# yacc2buss.net
KiCad netlist of a schematic drawn in EAGLE
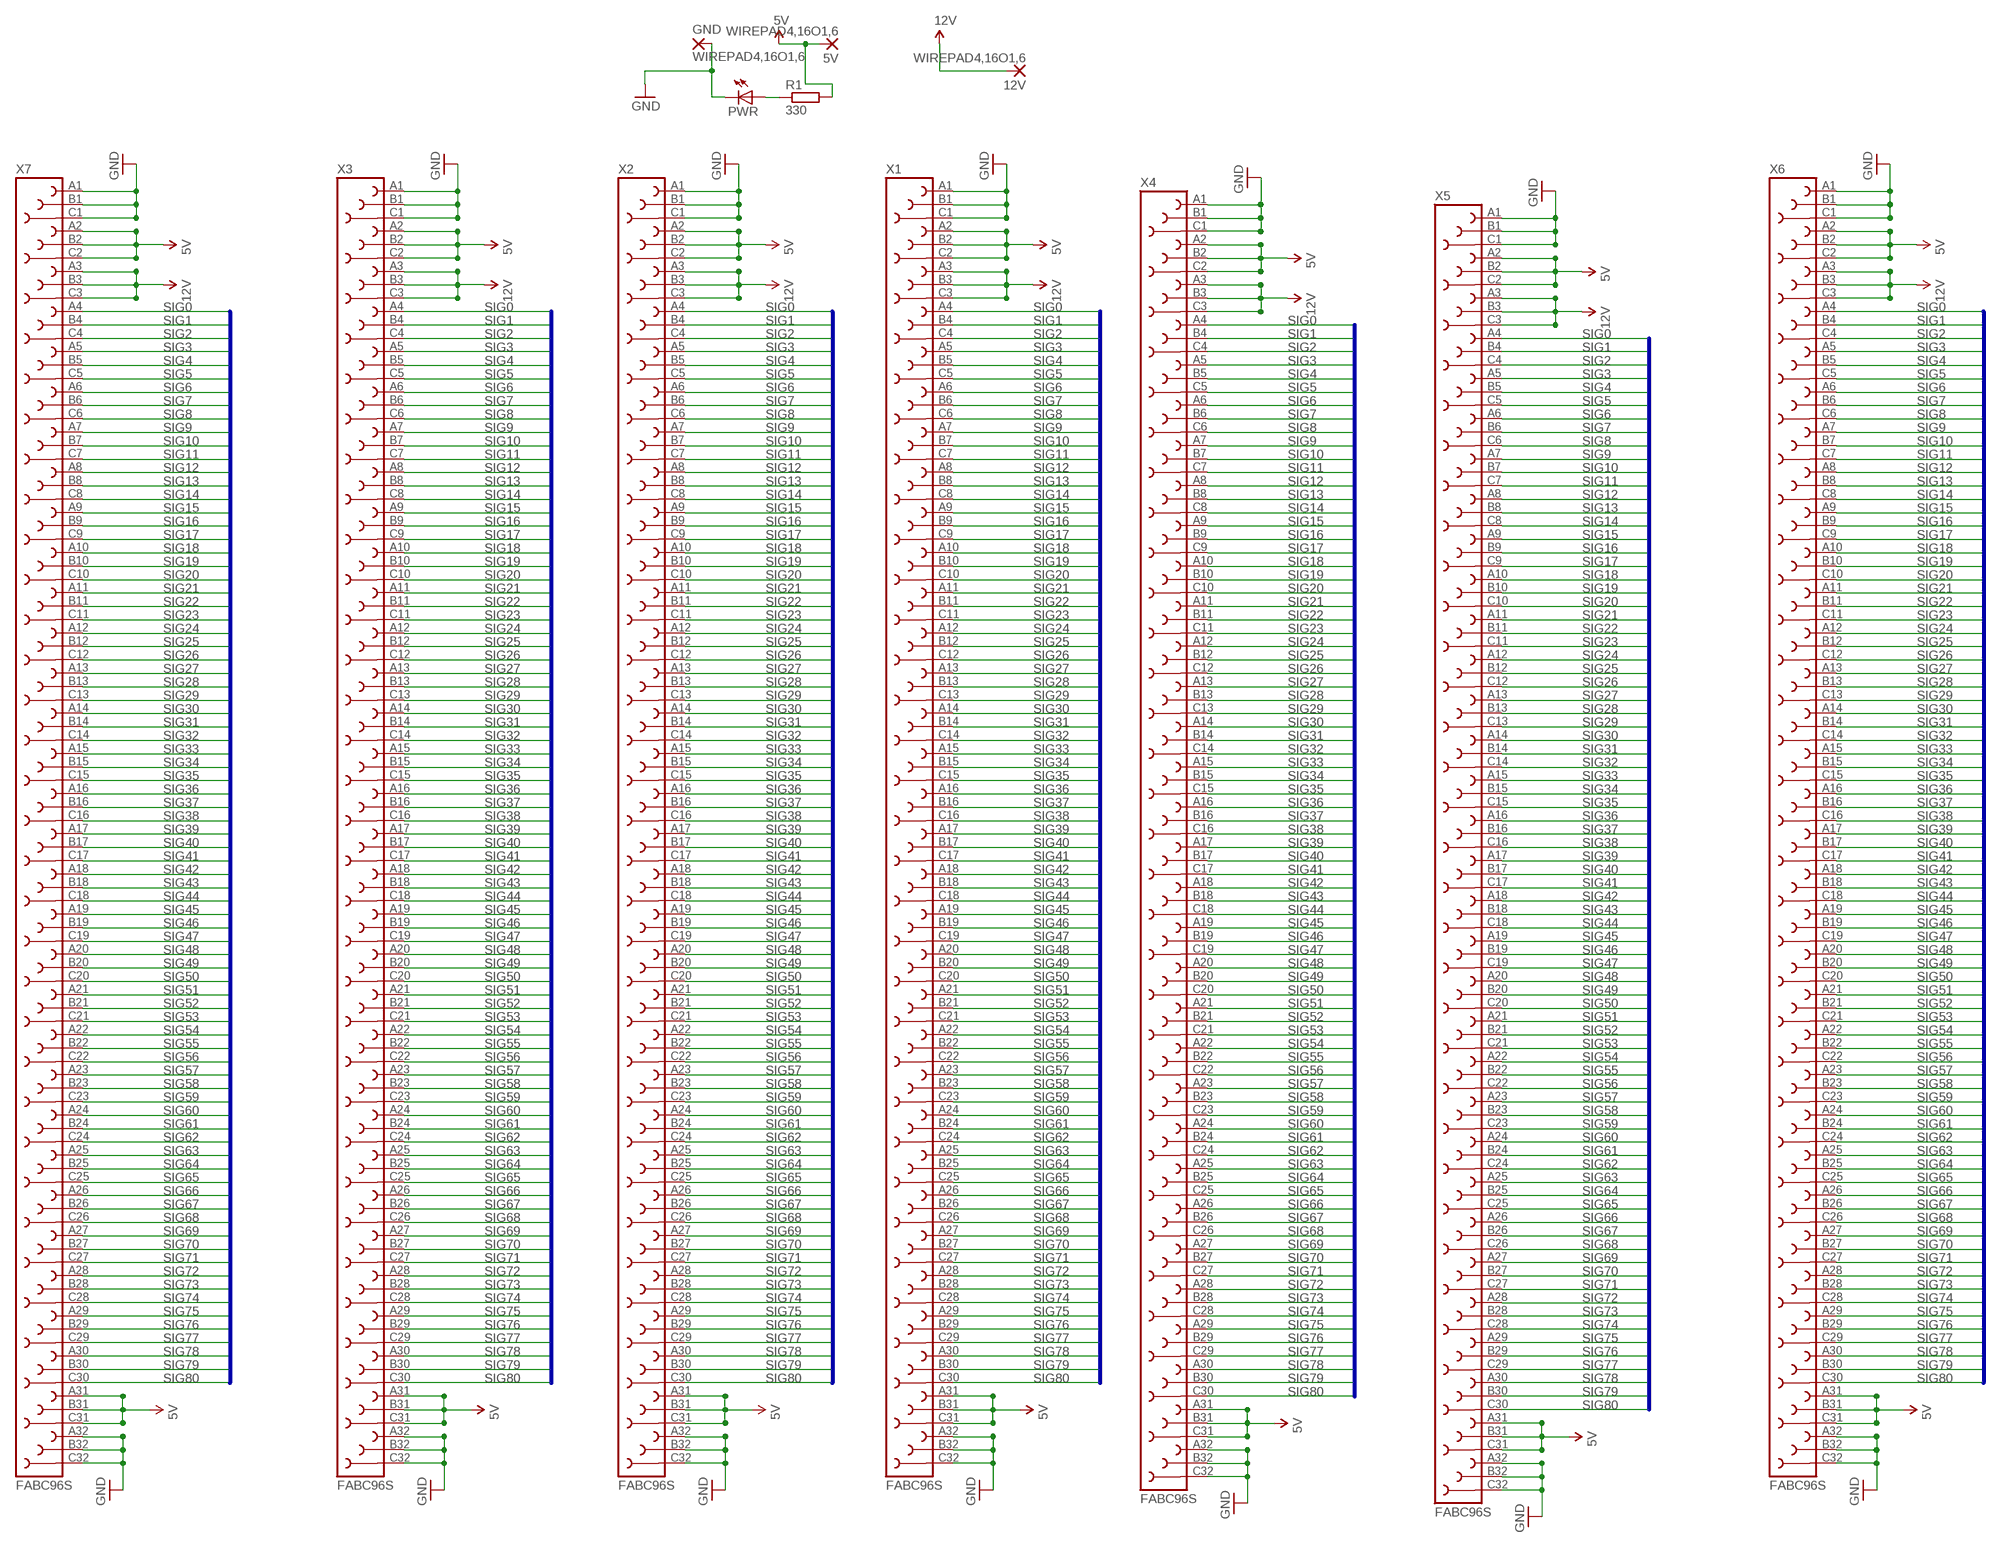
[diagram p0: schematic, sheet 1]

(export (version "E")
  (design (tool "Eeschema 10.0.6"))
  (components
    (comp (ref "5V")
      (value "WIREPAD4,16O1,6")
      (footprint "eagle-import:4,16O1,6")
      (libsource (lib "eagle-import") (part "WIREPAD4,16O1,6"))
    )
    (comp (ref "12V")
      (value "WIREPAD4,16O1,6")
      (footprint "eagle-import:4,16O1,6")
      (libsource (lib "eagle-import") (part "WIREPAD4,16O1,6"))
    )
    (comp (ref "GND")
      (value "WIREPAD4,16O1,6")
      (footprint "eagle-import:4,16O1,6")
      (libsource (lib "eagle-import") (part "WIREPAD4,16O1,6"))
    )
    (comp (ref "PWR")
      (value "LED5MM")
      (footprint "eagle-import:LED5MM")
      (libsource (lib "eagle-import") (part "LED5MM"))
    )
    (comp (ref "R1")
      (value "330")
      (footprint "eagle-import:0207_10")
      (libsource (lib "eagle-import") (part "R0207/10"))
    )
    (comp (ref "X1")
      (value "FABC96S")
      (footprint "eagle-import:FABC96S")
      (libsource (lib "eagle-import") (part "FABC96S"))
    )
    (comp (ref "X2")
      (value "FABC96S")
      (footprint "eagle-import:FABC96S")
      (libsource (lib "eagle-import") (part "FABC96S"))
    )
    (comp (ref "X3")
      (value "FABC96S")
      (footprint "eagle-import:FABC96S")
      (libsource (lib "eagle-import") (part "FABC96S"))
    )
    (comp (ref "X4")
      (value "FABC96S")
      (footprint "eagle-import:FABC96S")
      (libsource (lib "eagle-import") (part "FABC96S"))
    )
    (comp (ref "X5")
      (value "FABC96S")
      (footprint "eagle-import:FABC96S")
      (libsource (lib "eagle-import") (part "FABC96S"))
    )
    (comp (ref "X6")
      (value "FABC96S")
      (footprint "eagle-import:FABC96S")
      (libsource (lib "eagle-import") (part "FABC96S"))
    )
    (comp (ref "X7")
      (value "FABC96S")
      (footprint "eagle-import:FABC96S")
      (libsource (lib "eagle-import") (part "FABC96S"))
    )
  )
  (nets
    (net (code "1") (name "/SIG0") (class "Default")
      (node (ref "X1") (pin "A4") (pinfunction "A4_A4") (pintype "passive"))
      (node (ref "X2") (pin "A4") (pinfunction "A4_A4") (pintype "passive"))
      (node (ref "X3") (pin "A4") (pinfunction "A4_A4") (pintype "passive"))
      (node (ref "X4") (pin "A4") (pinfunction "A4_A4") (pintype "passive"))
      (node (ref "X5") (pin "A4") (pinfunction "A4_A4") (pintype "passive"))
      (node (ref "X6") (pin "A4") (pinfunction "A4_A4") (pintype "passive"))
      (node (ref "X7") (pin "A4") (pinfunction "A4_A4") (pintype "passive"))
    )
    (net (code "2") (name "/SIG1") (class "Default")
      (node (ref "X1") (pin "B4") (pinfunction "B4_B4") (pintype "passive"))
      (node (ref "X2") (pin "B4") (pinfunction "B4_B4") (pintype "passive"))
      (node (ref "X3") (pin "B4") (pinfunction "B4_B4") (pintype "passive"))
      (node (ref "X4") (pin "B4") (pinfunction "B4_B4") (pintype "passive"))
      (node (ref "X5") (pin "B4") (pinfunction "B4_B4") (pintype "passive"))
      (node (ref "X6") (pin "B4") (pinfunction "B4_B4") (pintype "passive"))
      (node (ref "X7") (pin "B4") (pinfunction "B4_B4") (pintype "passive"))
    )
    (net (code "3") (name "/SIG2") (class "Default")
      (node (ref "X1") (pin "C4") (pinfunction "C4_C4") (pintype "passive"))
      (node (ref "X2") (pin "C4") (pinfunction "C4_C4") (pintype "passive"))
      (node (ref "X3") (pin "C4") (pinfunction "C4_C4") (pintype "passive"))
      (node (ref "X4") (pin "C4") (pinfunction "C4_C4") (pintype "passive"))
      (node (ref "X5") (pin "C4") (pinfunction "C4_C4") (pintype "passive"))
      (node (ref "X6") (pin "C4") (pinfunction "C4_C4") (pintype "passive"))
      (node (ref "X7") (pin "C4") (pinfunction "C4_C4") (pintype "passive"))
    )
    (net (code "4") (name "/SIG3") (class "Default")
      (node (ref "X1") (pin "A5") (pinfunction "A5_A5") (pintype "passive"))
      (node (ref "X2") (pin "A5") (pinfunction "A5_A5") (pintype "passive"))
      (node (ref "X3") (pin "A5") (pinfunction "A5_A5") (pintype "passive"))
      (node (ref "X4") (pin "A5") (pinfunction "A5_A5") (pintype "passive"))
      (node (ref "X5") (pin "A5") (pinfunction "A5_A5") (pintype "passive"))
      (node (ref "X6") (pin "A5") (pinfunction "A5_A5") (pintype "passive"))
      (node (ref "X7") (pin "A5") (pinfunction "A5_A5") (pintype "passive"))
    )
    (net (code "5") (name "/SIG4") (class "Default")
      (node (ref "X1") (pin "B5") (pinfunction "B5_B5") (pintype "passive"))
      (node (ref "X2") (pin "B5") (pinfunction "B5_B5") (pintype "passive"))
      (node (ref "X3") (pin "B5") (pinfunction "B5_B5") (pintype "passive"))
      (node (ref "X4") (pin "B5") (pinfunction "B5_B5") (pintype "passive"))
      (node (ref "X5") (pin "B5") (pinfunction "B5_B5") (pintype "passive"))
      (node (ref "X6") (pin "B5") (pinfunction "B5_B5") (pintype "passive"))
      (node (ref "X7") (pin "B5") (pinfunction "B5_B5") (pintype "passive"))
    )
    (net (code "6") (name "/SIG5") (class "Default")
      (node (ref "X1") (pin "C5") (pinfunction "C5_C5") (pintype "passive"))
      (node (ref "X2") (pin "C5") (pinfunction "C5_C5") (pintype "passive"))
      (node (ref "X3") (pin "C5") (pinfunction "C5_C5") (pintype "passive"))
      (node (ref "X4") (pin "C5") (pinfunction "C5_C5") (pintype "passive"))
      (node (ref "X5") (pin "C5") (pinfunction "C5_C5") (pintype "passive"))
      (node (ref "X6") (pin "C5") (pinfunction "C5_C5") (pintype "passive"))
      (node (ref "X7") (pin "C5") (pinfunction "C5_C5") (pintype "passive"))
    )
    (net (code "7") (name "/SIG6") (class "Default")
      (node (ref "X1") (pin "A6") (pinfunction "A6_A6") (pintype "passive"))
      (node (ref "X2") (pin "A6") (pinfunction "A6_A6") (pintype "passive"))
      (node (ref "X3") (pin "A6") (pinfunction "A6_A6") (pintype "passive"))
      (node (ref "X4") (pin "A6") (pinfunction "A6_A6") (pintype "passive"))
      (node (ref "X5") (pin "A6") (pinfunction "A6_A6") (pintype "passive"))
      (node (ref "X6") (pin "A6") (pinfunction "A6_A6") (pintype "passive"))
      (node (ref "X7") (pin "A6") (pinfunction "A6_A6") (pintype "passive"))
    )
    (net (code "8") (name "/SIG7") (class "Default")
      (node (ref "X1") (pin "B6") (pinfunction "B6_B6") (pintype "passive"))
      (node (ref "X2") (pin "B6") (pinfunction "B6_B6") (pintype "passive"))
      (node (ref "X3") (pin "B6") (pinfunction "B6_B6") (pintype "passive"))
      (node (ref "X4") (pin "B6") (pinfunction "B6_B6") (pintype "passive"))
      (node (ref "X5") (pin "B6") (pinfunction "B6_B6") (pintype "passive"))
      (node (ref "X6") (pin "B6") (pinfunction "B6_B6") (pintype "passive"))
      (node (ref "X7") (pin "B6") (pinfunction "B6_B6") (pintype "passive"))
    )
    (net (code "9") (name "/SIG8") (class "Default")
      (node (ref "X1") (pin "C6") (pinfunction "C6_C6") (pintype "passive"))
      (node (ref "X2") (pin "C6") (pinfunction "C6_C6") (pintype "passive"))
      (node (ref "X3") (pin "C6") (pinfunction "C6_C6") (pintype "passive"))
      (node (ref "X4") (pin "C6") (pinfunction "C6_C6") (pintype "passive"))
      (node (ref "X5") (pin "C6") (pinfunction "C6_C6") (pintype "passive"))
      (node (ref "X6") (pin "C6") (pinfunction "C6_C6") (pintype "passive"))
      (node (ref "X7") (pin "C6") (pinfunction "C6_C6") (pintype "passive"))
    )
    (net (code "10") (name "/SIG9") (class "Default")
      (node (ref "X1") (pin "A7") (pinfunction "A7_A7") (pintype "passive"))
      (node (ref "X2") (pin "A7") (pinfunction "A7_A7") (pintype "passive"))
      (node (ref "X3") (pin "A7") (pinfunction "A7_A7") (pintype "passive"))
      (node (ref "X4") (pin "A7") (pinfunction "A7_A7") (pintype "passive"))
      (node (ref "X5") (pin "A7") (pinfunction "A7_A7") (pintype "passive"))
      (node (ref "X6") (pin "A7") (pinfunction "A7_A7") (pintype "passive"))
      (node (ref "X7") (pin "A7") (pinfunction "A7_A7") (pintype "passive"))
    )
    (net (code "11") (name "/SIG10") (class "Default")
      (node (ref "X1") (pin "B7") (pinfunction "B7_B7") (pintype "passive"))
      (node (ref "X2") (pin "B7") (pinfunction "B7_B7") (pintype "passive"))
      (node (ref "X3") (pin "B7") (pinfunction "B7_B7") (pintype "passive"))
      (node (ref "X4") (pin "B7") (pinfunction "B7_B7") (pintype "passive"))
      (node (ref "X5") (pin "B7") (pinfunction "B7_B7") (pintype "passive"))
      (node (ref "X6") (pin "B7") (pinfunction "B7_B7") (pintype "passive"))
      (node (ref "X7") (pin "B7") (pinfunction "B7_B7") (pintype "passive"))
    )
    (net (code "12") (name "/SIG11") (class "Default")
      (node (ref "X1") (pin "C7") (pinfunction "C7_C7") (pintype "passive"))
      (node (ref "X2") (pin "C7") (pinfunction "C7_C7") (pintype "passive"))
      (node (ref "X3") (pin "C7") (pinfunction "C7_C7") (pintype "passive"))
      (node (ref "X4") (pin "C7") (pinfunction "C7_C7") (pintype "passive"))
      (node (ref "X5") (pin "C7") (pinfunction "C7_C7") (pintype "passive"))
      (node (ref "X6") (pin "C7") (pinfunction "C7_C7") (pintype "passive"))
      (node (ref "X7") (pin "C7") (pinfunction "C7_C7") (pintype "passive"))
    )
    (net (code "13") (name "/SIG12") (class "Default")
      (node (ref "X1") (pin "A8") (pinfunction "A8_A8") (pintype "passive"))
      (node (ref "X2") (pin "A8") (pinfunction "A8_A8") (pintype "passive"))
      (node (ref "X3") (pin "A8") (pinfunction "A8_A8") (pintype "passive"))
      (node (ref "X4") (pin "A8") (pinfunction "A8_A8") (pintype "passive"))
      (node (ref "X5") (pin "A8") (pinfunction "A8_A8") (pintype "passive"))
      (node (ref "X6") (pin "A8") (pinfunction "A8_A8") (pintype "passive"))
      (node (ref "X7") (pin "A8") (pinfunction "A8_A8") (pintype "passive"))
    )
    (net (code "14") (name "/SIG13") (class "Default")
      (node (ref "X1") (pin "B8") (pinfunction "B8_B8") (pintype "passive"))
      (node (ref "X2") (pin "B8") (pinfunction "B8_B8") (pintype "passive"))
      (node (ref "X3") (pin "B8") (pinfunction "B8_B8") (pintype "passive"))
      (node (ref "X4") (pin "B8") (pinfunction "B8_B8") (pintype "passive"))
      (node (ref "X5") (pin "B8") (pinfunction "B8_B8") (pintype "passive"))
      (node (ref "X6") (pin "B8") (pinfunction "B8_B8") (pintype "passive"))
      (node (ref "X7") (pin "B8") (pinfunction "B8_B8") (pintype "passive"))
    )
    (net (code "15") (name "/SIG14") (class "Default")
      (node (ref "X1") (pin "C8") (pinfunction "C8_C8") (pintype "passive"))
      (node (ref "X2") (pin "C8") (pinfunction "C8_C8") (pintype "passive"))
      (node (ref "X3") (pin "C8") (pinfunction "C8_C8") (pintype "passive"))
      (node (ref "X4") (pin "C8") (pinfunction "C8_C8") (pintype "passive"))
      (node (ref "X5") (pin "C8") (pinfunction "C8_C8") (pintype "passive"))
      (node (ref "X6") (pin "C8") (pinfunction "C8_C8") (pintype "passive"))
      (node (ref "X7") (pin "C8") (pinfunction "C8_C8") (pintype "passive"))
    )
    (net (code "16") (name "/SIG15") (class "Default")
      (node (ref "X1") (pin "A9") (pinfunction "A9_A9") (pintype "passive"))
      (node (ref "X2") (pin "A9") (pinfunction "A9_A9") (pintype "passive"))
      (node (ref "X3") (pin "A9") (pinfunction "A9_A9") (pintype "passive"))
      (node (ref "X4") (pin "A9") (pinfunction "A9_A9") (pintype "passive"))
      (node (ref "X5") (pin "A9") (pinfunction "A9_A9") (pintype "passive"))
      (node (ref "X6") (pin "A9") (pinfunction "A9_A9") (pintype "passive"))
      (node (ref "X7") (pin "A9") (pinfunction "A9_A9") (pintype "passive"))
    )
    (net (code "17") (name "/SIG16") (class "Default")
      (node (ref "X1") (pin "B9") (pinfunction "B9_B9") (pintype "passive"))
      (node (ref "X2") (pin "B9") (pinfunction "B9_B9") (pintype "passive"))
      (node (ref "X3") (pin "B9") (pinfunction "B9_B9") (pintype "passive"))
      (node (ref "X4") (pin "B9") (pinfunction "B9_B9") (pintype "passive"))
      (node (ref "X5") (pin "B9") (pinfunction "B9_B9") (pintype "passive"))
      (node (ref "X6") (pin "B9") (pinfunction "B9_B9") (pintype "passive"))
      (node (ref "X7") (pin "B9") (pinfunction "B9_B9") (pintype "passive"))
    )
    (net (code "18") (name "/SIG17") (class "Default")
      (node (ref "X1") (pin "C9") (pinfunction "C9_C9") (pintype "passive"))
      (node (ref "X2") (pin "C9") (pinfunction "C9_C9") (pintype "passive"))
      (node (ref "X3") (pin "C9") (pinfunction "C9_C9") (pintype "passive"))
      (node (ref "X4") (pin "C9") (pinfunction "C9_C9") (pintype "passive"))
      (node (ref "X5") (pin "C9") (pinfunction "C9_C9") (pintype "passive"))
      (node (ref "X6") (pin "C9") (pinfunction "C9_C9") (pintype "passive"))
      (node (ref "X7") (pin "C9") (pinfunction "C9_C9") (pintype "passive"))
    )
    (net (code "19") (name "/SIG18") (class "Default")
      (node (ref "X1") (pin "A10") (pinfunction "A10_A10") (pintype "passive"))
      (node (ref "X2") (pin "A10") (pinfunction "A10_A10") (pintype "passive"))
      (node (ref "X3") (pin "A10") (pinfunction "A10_A10") (pintype "passive"))
      (node (ref "X4") (pin "A10") (pinfunction "A10_A10") (pintype "passive"))
      (node (ref "X5") (pin "A10") (pinfunction "A10_A10") (pintype "passive"))
      (node (ref "X6") (pin "A10") (pinfunction "A10_A10") (pintype "passive"))
      (node (ref "X7") (pin "A10") (pinfunction "A10_A10") (pintype "passive"))
    )
    (net (code "20") (name "/SIG19") (class "Default")
      (node (ref "X1") (pin "B10") (pinfunction "B10_B10") (pintype "passive"))
      (node (ref "X2") (pin "B10") (pinfunction "B10_B10") (pintype "passive"))
      (node (ref "X3") (pin "B10") (pinfunction "B10_B10") (pintype "passive"))
      (node (ref "X4") (pin "B10") (pinfunction "B10_B10") (pintype "passive"))
      (node (ref "X5") (pin "B10") (pinfunction "B10_B10") (pintype "passive"))
      (node (ref "X6") (pin "B10") (pinfunction "B10_B10") (pintype "passive"))
      (node (ref "X7") (pin "B10") (pinfunction "B10_B10") (pintype "passive"))
    )
    (net (code "21") (name "/SIG20") (class "Default")
      (node (ref "X1") (pin "C10") (pinfunction "C10_C10") (pintype "passive"))
      (node (ref "X2") (pin "C10") (pinfunction "C10_C10") (pintype "passive"))
      (node (ref "X3") (pin "C10") (pinfunction "C10_C10") (pintype "passive"))
      (node (ref "X4") (pin "C10") (pinfunction "C10_C10") (pintype "passive"))
      (node (ref "X5") (pin "C10") (pinfunction "C10_C10") (pintype "passive"))
      (node (ref "X6") (pin "C10") (pinfunction "C10_C10") (pintype "passive"))
      (node (ref "X7") (pin "C10") (pinfunction "C10_C10") (pintype "passive"))
    )
    (net (code "22") (name "/SIG21") (class "Default")
      (node (ref "X1") (pin "A11") (pinfunction "A11_A11") (pintype "passive"))
      (node (ref "X2") (pin "A11") (pinfunction "A11_A11") (pintype "passive"))
      (node (ref "X3") (pin "A11") (pinfunction "A11_A11") (pintype "passive"))
      (node (ref "X4") (pin "A11") (pinfunction "A11_A11") (pintype "passive"))
      (node (ref "X5") (pin "A11") (pinfunction "A11_A11") (pintype "passive"))
      (node (ref "X6") (pin "A11") (pinfunction "A11_A11") (pintype "passive"))
      (node (ref "X7") (pin "A11") (pinfunction "A11_A11") (pintype "passive"))
    )
    (net (code "23") (name "/SIG22") (class "Default")
      (node (ref "X1") (pin "B11") (pinfunction "B11_B11") (pintype "passive"))
      (node (ref "X2") (pin "B11") (pinfunction "B11_B11") (pintype "passive"))
      (node (ref "X3") (pin "B11") (pinfunction "B11_B11") (pintype "passive"))
      (node (ref "X4") (pin "B11") (pinfunction "B11_B11") (pintype "passive"))
      (node (ref "X5") (pin "B11") (pinfunction "B11_B11") (pintype "passive"))
      (node (ref "X6") (pin "B11") (pinfunction "B11_B11") (pintype "passive"))
      (node (ref "X7") (pin "B11") (pinfunction "B11_B11") (pintype "passive"))
    )
    (net (code "24") (name "/SIG23") (class "Default")
      (node (ref "X1") (pin "C11") (pinfunction "C11_C11") (pintype "passive"))
      (node (ref "X2") (pin "C11") (pinfunction "C11_C11") (pintype "passive"))
      (node (ref "X3") (pin "C11") (pinfunction "C11_C11") (pintype "passive"))
      (node (ref "X4") (pin "C11") (pinfunction "C11_C11") (pintype "passive"))
      (node (ref "X5") (pin "C11") (pinfunction "C11_C11") (pintype "passive"))
      (node (ref "X6") (pin "C11") (pinfunction "C11_C11") (pintype "passive"))
      (node (ref "X7") (pin "C11") (pinfunction "C11_C11") (pintype "passive"))
    )
    (net (code "25") (name "/SIG24") (class "Default")
      (node (ref "X1") (pin "A12") (pinfunction "A12_A12") (pintype "passive"))
      (node (ref "X2") (pin "A12") (pinfunction "A12_A12") (pintype "passive"))
      (node (ref "X3") (pin "A12") (pinfunction "A12_A12") (pintype "passive"))
      (node (ref "X4") (pin "A12") (pinfunction "A12_A12") (pintype "passive"))
      (node (ref "X5") (pin "A12") (pinfunction "A12_A12") (pintype "passive"))
      (node (ref "X6") (pin "A12") (pinfunction "A12_A12") (pintype "passive"))
      (node (ref "X7") (pin "A12") (pinfunction "A12_A12") (pintype "passive"))
    )
    (net (code "26") (name "/SIG25") (class "Default")
      (node (ref "X1") (pin "B12") (pinfunction "B12_B12") (pintype "passive"))
      (node (ref "X2") (pin "B12") (pinfunction "B12_B12") (pintype "passive"))
      (node (ref "X3") (pin "B12") (pinfunction "B12_B12") (pintype "passive"))
      (node (ref "X4") (pin "B12") (pinfunction "B12_B12") (pintype "passive"))
      (node (ref "X5") (pin "B12") (pinfunction "B12_B12") (pintype "passive"))
      (node (ref "X6") (pin "B12") (pinfunction "B12_B12") (pintype "passive"))
      (node (ref "X7") (pin "B12") (pinfunction "B12_B12") (pintype "passive"))
    )
    (net (code "27") (name "/SIG26") (class "Default")
      (node (ref "X1") (pin "C12") (pinfunction "C12_C12") (pintype "passive"))
      (node (ref "X2") (pin "C12") (pinfunction "C12_C12") (pintype "passive"))
      (node (ref "X3") (pin "C12") (pinfunction "C12_C12") (pintype "passive"))
      (node (ref "X4") (pin "C12") (pinfunction "C12_C12") (pintype "passive"))
      (node (ref "X5") (pin "C12") (pinfunction "C12_C12") (pintype "passive"))
      (node (ref "X6") (pin "C12") (pinfunction "C12_C12") (pintype "passive"))
      (node (ref "X7") (pin "C12") (pinfunction "C12_C12") (pintype "passive"))
    )
    (net (code "28") (name "/SIG27") (class "Default")
      (node (ref "X1") (pin "A13") (pinfunction "A13_A13") (pintype "passive"))
      (node (ref "X2") (pin "A13") (pinfunction "A13_A13") (pintype "passive"))
      (node (ref "X3") (pin "A13") (pinfunction "A13_A13") (pintype "passive"))
      (node (ref "X4") (pin "A13") (pinfunction "A13_A13") (pintype "passive"))
      (node (ref "X5") (pin "A13") (pinfunction "A13_A13") (pintype "passive"))
      (node (ref "X6") (pin "A13") (pinfunction "A13_A13") (pintype "passive"))
      (node (ref "X7") (pin "A13") (pinfunction "A13_A13") (pintype "passive"))
    )
    (net (code "29") (name "/SIG28") (class "Default")
      (node (ref "X1") (pin "B13") (pinfunction "B13_B13") (pintype "passive"))
      (node (ref "X2") (pin "B13") (pinfunction "B13_B13") (pintype "passive"))
      (node (ref "X3") (pin "B13") (pinfunction "B13_B13") (pintype "passive"))
      (node (ref "X4") (pin "B13") (pinfunction "B13_B13") (pintype "passive"))
      (node (ref "X5") (pin "B13") (pinfunction "B13_B13") (pintype "passive"))
      (node (ref "X6") (pin "B13") (pinfunction "B13_B13") (pintype "passive"))
      (node (ref "X7") (pin "B13") (pinfunction "B13_B13") (pintype "passive"))
    )
    (net (code "30") (name "/SIG29") (class "Default")
      (node (ref "X1") (pin "C13") (pinfunction "C13_C13") (pintype "passive"))
      (node (ref "X2") (pin "C13") (pinfunction "C13_C13") (pintype "passive"))
      (node (ref "X3") (pin "C13") (pinfunction "C13_C13") (pintype "passive"))
      (node (ref "X4") (pin "C13") (pinfunction "C13_C13") (pintype "passive"))
      (node (ref "X5") (pin "C13") (pinfunction "C13_C13") (pintype "passive"))
      (node (ref "X6") (pin "C13") (pinfunction "C13_C13") (pintype "passive"))
      (node (ref "X7") (pin "C13") (pinfunction "C13_C13") (pintype "passive"))
    )
    (net (code "31") (name "/SIG30") (class "Default")
      (node (ref "X1") (pin "A14") (pinfunction "A14_A14") (pintype "passive"))
      (node (ref "X2") (pin "A14") (pinfunction "A14_A14") (pintype "passive"))
      (node (ref "X3") (pin "A14") (pinfunction "A14_A14") (pintype "passive"))
      (node (ref "X4") (pin "A14") (pinfunction "A14_A14") (pintype "passive"))
      (node (ref "X5") (pin "A14") (pinfunction "A14_A14") (pintype "passive"))
      (node (ref "X6") (pin "A14") (pinfunction "A14_A14") (pintype "passive"))
      (node (ref "X7") (pin "A14") (pinfunction "A14_A14") (pintype "passive"))
    )
    (net (code "32") (name "/SIG31") (class "Default")
      (node (ref "X1") (pin "B14") (pinfunction "B14_B14") (pintype "passive"))
      (node (ref "X2") (pin "B14") (pinfunction "B14_B14") (pintype "passive"))
      (node (ref "X3") (pin "B14") (pinfunction "B14_B14") (pintype "passive"))
      (node (ref "X4") (pin "B14") (pinfunction "B14_B14") (pintype "passive"))
      (node (ref "X5") (pin "B14") (pinfunction "B14_B14") (pintype "passive"))
      (node (ref "X6") (pin "B14") (pinfunction "B14_B14") (pintype "passive"))
      (node (ref "X7") (pin "B14") (pinfunction "B14_B14") (pintype "passive"))
    )
    (net (code "33") (name "/SIG32") (class "Default")
      (node (ref "X1") (pin "C14") (pinfunction "C14_C14") (pintype "passive"))
      (node (ref "X2") (pin "C14") (pinfunction "C14_C14") (pintype "passive"))
      (node (ref "X3") (pin "C14") (pinfunction "C14_C14") (pintype "passive"))
      (node (ref "X4") (pin "C14") (pinfunction "C14_C14") (pintype "passive"))
      (node (ref "X5") (pin "C14") (pinfunction "C14_C14") (pintype "passive"))
      (node (ref "X6") (pin "C14") (pinfunction "C14_C14") (pintype "passive"))
      (node (ref "X7") (pin "C14") (pinfunction "C14_C14") (pintype "passive"))
    )
    (net (code "34") (name "/SIG33") (class "Default")
      (node (ref "X1") (pin "A15") (pinfunction "A15_A15") (pintype "passive"))
      (node (ref "X2") (pin "A15") (pinfunction "A15_A15") (pintype "passive"))
      (node (ref "X3") (pin "A15") (pinfunction "A15_A15") (pintype "passive"))
      (node (ref "X4") (pin "A15") (pinfunction "A15_A15") (pintype "passive"))
      (node (ref "X5") (pin "A15") (pinfunction "A15_A15") (pintype "passive"))
      (node (ref "X6") (pin "A15") (pinfunction "A15_A15") (pintype "passive"))
      (node (ref "X7") (pin "A15") (pinfunction "A15_A15") (pintype "passive"))
    )
    (net (code "35") (name "/SIG34") (class "Default")
      (node (ref "X1") (pin "B15") (pinfunction "B15_B15") (pintype "passive"))
      (node (ref "X2") (pin "B15") (pinfunction "B15_B15") (pintype "passive"))
      (node (ref "X3") (pin "B15") (pinfunction "B15_B15") (pintype "passive"))
      (node (ref "X4") (pin "B15") (pinfunction "B15_B15") (pintype "passive"))
      (node (ref "X5") (pin "B15") (pinfunction "B15_B15") (pintype "passive"))
      (node (ref "X6") (pin "B15") (pinfunction "B15_B15") (pintype "passive"))
      (node (ref "X7") (pin "B15") (pinfunction "B15_B15") (pintype "passive"))
    )
    (net (code "36") (name "/SIG35") (class "Default")
      (node (ref "X1") (pin "C15") (pinfunction "C15_C15") (pintype "passive"))
      (node (ref "X2") (pin "C15") (pinfunction "C15_C15") (pintype "passive"))
      (node (ref "X3") (pin "C15") (pinfunction "C15_C15") (pintype "passive"))
      (node (ref "X4") (pin "C15") (pinfunction "C15_C15") (pintype "passive"))
      (node (ref "X5") (pin "C15") (pinfunction "C15_C15") (pintype "passive"))
      (node (ref "X6") (pin "C15") (pinfunction "C15_C15") (pintype "passive"))
      (node (ref "X7") (pin "C15") (pinfunction "C15_C15") (pintype "passive"))
    )
    (net (code "37") (name "/SIG36") (class "Default")
      (node (ref "X1") (pin "A16") (pinfunction "A16_A16") (pintype "passive"))
      (node (ref "X2") (pin "A16") (pinfunction "A16_A16") (pintype "passive"))
      (node (ref "X3") (pin "A16") (pinfunction "A16_A16") (pintype "passive"))
      (node (ref "X4") (pin "A16") (pinfunction "A16_A16") (pintype "passive"))
      (node (ref "X5") (pin "A16") (pinfunction "A16_A16") (pintype "passive"))
      (node (ref "X6") (pin "A16") (pinfunction "A16_A16") (pintype "passive"))
      (node (ref "X7") (pin "A16") (pinfunction "A16_A16") (pintype "passive"))
    )
    (net (code "38") (name "/SIG37") (class "Default")
      (node (ref "X1") (pin "B16") (pinfunction "B16_B16") (pintype "passive"))
      (node (ref "X2") (pin "B16") (pinfunction "B16_B16") (pintype "passive"))
      (node (ref "X3") (pin "B16") (pinfunction "B16_B16") (pintype "passive"))
      (node (ref "X4") (pin "B16") (pinfunction "B16_B16") (pintype "passive"))
      (node (ref "X5") (pin "B16") (pinfunction "B16_B16") (pintype "passive"))
      (node (ref "X6") (pin "B16") (pinfunction "B16_B16") (pintype "passive"))
      (node (ref "X7") (pin "B16") (pinfunction "B16_B16") (pintype "passive"))
    )
    (net (code "39") (name "/SIG38") (class "Default")
      (node (ref "X1") (pin "C16") (pinfunction "C16_C16") (pintype "passive"))
      (node (ref "X2") (pin "C16") (pinfunction "C16_C16") (pintype "passive"))
      (node (ref "X3") (pin "C16") (pinfunction "C16_C16") (pintype "passive"))
      (node (ref "X4") (pin "C16") (pinfunction "C16_C16") (pintype "passive"))
      (node (ref "X5") (pin "C16") (pinfunction "C16_C16") (pintype "passive"))
      (node (ref "X6") (pin "C16") (pinfunction "C16_C16") (pintype "passive"))
      (node (ref "X7") (pin "C16") (pinfunction "C16_C16") (pintype "passive"))
    )
    (net (code "40") (name "/SIG39") (class "Default")
      (node (ref "X1") (pin "A17") (pinfunction "A17_A17") (pintype "passive"))
      (node (ref "X2") (pin "A17") (pinfunction "A17_A17") (pintype "passive"))
      (node (ref "X3") (pin "A17") (pinfunction "A17_A17") (pintype "passive"))
      (node (ref "X4") (pin "A17") (pinfunction "A17_A17") (pintype "passive"))
      (node (ref "X5") (pin "A17") (pinfunction "A17_A17") (pintype "passive"))
      (node (ref "X6") (pin "A17") (pinfunction "A17_A17") (pintype "passive"))
      (node (ref "X7") (pin "A17") (pinfunction "A17_A17") (pintype "passive"))
    )
    (net (code "41") (name "/SIG40") (class "Default")
      (node (ref "X1") (pin "B17") (pinfunction "B17_B17") (pintype "passive"))
      (node (ref "X2") (pin "B17") (pinfunction "B17_B17") (pintype "passive"))
      (node (ref "X3") (pin "B17") (pinfunction "B17_B17") (pintype "passive"))
      (node (ref "X4") (pin "B17") (pinfunction "B17_B17") (pintype "passive"))
      (node (ref "X5") (pin "B17") (pinfunction "B17_B17") (pintype "passive"))
      (node (ref "X6") (pin "B17") (pinfunction "B17_B17") (pintype "passive"))
      (node (ref "X7") (pin "B17") (pinfunction "B17_B17") (pintype "passive"))
    )
    (net (code "42") (name "/SIG41") (class "Default")
      (node (ref "X1") (pin "C17") (pinfunction "C17_C17") (pintype "passive"))
      (node (ref "X2") (pin "C17") (pinfunction "C17_C17") (pintype "passive"))
      (node (ref "X3") (pin "C17") (pinfunction "C17_C17") (pintype "passive"))
      (node (ref "X4") (pin "C17") (pinfunction "C17_C17") (pintype "passive"))
      (node (ref "X5") (pin "C17") (pinfunction "C17_C17") (pintype "passive"))
      (node (ref "X6") (pin "C17") (pinfunction "C17_C17") (pintype "passive"))
      (node (ref "X7") (pin "C17") (pinfunction "C17_C17") (pintype "passive"))
    )
    (net (code "43") (name "/SIG42") (class "Default")
      (node (ref "X1") (pin "A18") (pinfunction "A18_A18") (pintype "passive"))
      (node (ref "X2") (pin "A18") (pinfunction "A18_A18") (pintype "passive"))
      (node (ref "X3") (pin "A18") (pinfunction "A18_A18") (pintype "passive"))
      (node (ref "X4") (pin "A18") (pinfunction "A18_A18") (pintype "passive"))
      (node (ref "X5") (pin "A18") (pinfunction "A18_A18") (pintype "passive"))
      (node (ref "X6") (pin "A18") (pinfunction "A18_A18") (pintype "passive"))
      (node (ref "X7") (pin "A18") (pinfunction "A18_A18") (pintype "passive"))
    )
    (net (code "44") (name "/SIG43") (class "Default")
      (node (ref "X1") (pin "B18") (pinfunction "B18_B18") (pintype "passive"))
      (node (ref "X2") (pin "B18") (pinfunction "B18_B18") (pintype "passive"))
      (node (ref "X3") (pin "B18") (pinfunction "B18_B18") (pintype "passive"))
      (node (ref "X4") (pin "B18") (pinfunction "B18_B18") (pintype "passive"))
      (node (ref "X5") (pin "B18") (pinfunction "B18_B18") (pintype "passive"))
      (node (ref "X6") (pin "B18") (pinfunction "B18_B18") (pintype "passive"))
      (node (ref "X7") (pin "B18") (pinfunction "B18_B18") (pintype "passive"))
    )
    (net (code "45") (name "/SIG44") (class "Default")
      (node (ref "X1") (pin "C18") (pinfunction "C18_C18") (pintype "passive"))
      (node (ref "X2") (pin "C18") (pinfunction "C18_C18") (pintype "passive"))
      (node (ref "X3") (pin "C18") (pinfunction "C18_C18") (pintype "passive"))
      (node (ref "X4") (pin "C18") (pinfunction "C18_C18") (pintype "passive"))
      (node (ref "X5") (pin "C18") (pinfunction "C18_C18") (pintype "passive"))
      (node (ref "X6") (pin "C18") (pinfunction "C18_C18") (pintype "passive"))
      (node (ref "X7") (pin "C18") (pinfunction "C18_C18") (pintype "passive"))
    )
    (net (code "46") (name "/SIG45") (class "Default")
      (node (ref "X1") (pin "A19") (pinfunction "A19_A19") (pintype "passive"))
      (node (ref "X2") (pin "A19") (pinfunction "A19_A19") (pintype "passive"))
      (node (ref "X3") (pin "A19") (pinfunction "A19_A19") (pintype "passive"))
      (node (ref "X4") (pin "A19") (pinfunction "A19_A19") (pintype "passive"))
      (node (ref "X5") (pin "A19") (pinfunction "A19_A19") (pintype "passive"))
      (node (ref "X6") (pin "A19") (pinfunction "A19_A19") (pintype "passive"))
      (node (ref "X7") (pin "A19") (pinfunction "A19_A19") (pintype "passive"))
    )
    (net (code "47") (name "/SIG46") (class "Default")
      (node (ref "X1") (pin "B19") (pinfunction "B19_B19") (pintype "passive"))
      (node (ref "X2") (pin "B19") (pinfunction "B19_B19") (pintype "passive"))
      (node (ref "X3") (pin "B19") (pinfunction "B19_B19") (pintype "passive"))
      (node (ref "X4") (pin "B19") (pinfunction "B19_B19") (pintype "passive"))
      (node (ref "X5") (pin "B19") (pinfunction "B19_B19") (pintype "passive"))
      (node (ref "X6") (pin "B19") (pinfunction "B19_B19") (pintype "passive"))
      (node (ref "X7") (pin "B19") (pinfunction "B19_B19") (pintype "passive"))
    )
    (net (code "48") (name "/SIG47") (class "Default")
      (node (ref "X1") (pin "C19") (pinfunction "C19_C19") (pintype "passive"))
      (node (ref "X2") (pin "C19") (pinfunction "C19_C19") (pintype "passive"))
      (node (ref "X3") (pin "C19") (pinfunction "C19_C19") (pintype "passive"))
      (node (ref "X4") (pin "C19") (pinfunction "C19_C19") (pintype "passive"))
      (node (ref "X5") (pin "C19") (pinfunction "C19_C19") (pintype "passive"))
      (node (ref "X6") (pin "C19") (pinfunction "C19_C19") (pintype "passive"))
      (node (ref "X7") (pin "C19") (pinfunction "C19_C19") (pintype "passive"))
    )
    (net (code "49") (name "/SIG48") (class "Default")
      (node (ref "X1") (pin "A20") (pinfunction "A20_A20") (pintype "passive"))
      (node (ref "X2") (pin "A20") (pinfunction "A20_A20") (pintype "passive"))
      (node (ref "X3") (pin "A20") (pinfunction "A20_A20") (pintype "passive"))
      (node (ref "X4") (pin "A20") (pinfunction "A20_A20") (pintype "passive"))
      (node (ref "X5") (pin "A20") (pinfunction "A20_A20") (pintype "passive"))
      (node (ref "X6") (pin "A20") (pinfunction "A20_A20") (pintype "passive"))
      (node (ref "X7") (pin "A20") (pinfunction "A20_A20") (pintype "passive"))
    )
    (net (code "50") (name "/SIG49") (class "Default")
      (node (ref "X1") (pin "B20") (pinfunction "B20_B20") (pintype "passive"))
      (node (ref "X2") (pin "B20") (pinfunction "B20_B20") (pintype "passive"))
      (node (ref "X3") (pin "B20") (pinfunction "B20_B20") (pintype "passive"))
      (node (ref "X4") (pin "B20") (pinfunction "B20_B20") (pintype "passive"))
      (node (ref "X5") (pin "B20") (pinfunction "B20_B20") (pintype "passive"))
      (node (ref "X6") (pin "B20") (pinfunction "B20_B20") (pintype "passive"))
      (node (ref "X7") (pin "B20") (pinfunction "B20_B20") (pintype "passive"))
    )
    (net (code "51") (name "/SIG50") (class "Default")
      (node (ref "X1") (pin "C20") (pinfunction "C20_C20") (pintype "passive"))
      (node (ref "X2") (pin "C20") (pinfunction "C20_C20") (pintype "passive"))
      (node (ref "X3") (pin "C20") (pinfunction "C20_C20") (pintype "passive"))
      (node (ref "X4") (pin "C20") (pinfunction "C20_C20") (pintype "passive"))
      (node (ref "X5") (pin "C20") (pinfunction "C20_C20") (pintype "passive"))
      (node (ref "X6") (pin "C20") (pinfunction "C20_C20") (pintype "passive"))
      (node (ref "X7") (pin "C20") (pinfunction "C20_C20") (pintype "passive"))
    )
    (net (code "52") (name "/SIG51") (class "Default")
      (node (ref "X1") (pin "A21") (pinfunction "A21_A21") (pintype "passive"))
      (node (ref "X2") (pin "A21") (pinfunction "A21_A21") (pintype "passive"))
      (node (ref "X3") (pin "A21") (pinfunction "A21_A21") (pintype "passive"))
      (node (ref "X4") (pin "A21") (pinfunction "A21_A21") (pintype "passive"))
      (node (ref "X5") (pin "A21") (pinfunction "A21_A21") (pintype "passive"))
      (node (ref "X6") (pin "A21") (pinfunction "A21_A21") (pintype "passive"))
      (node (ref "X7") (pin "A21") (pinfunction "A21_A21") (pintype "passive"))
    )
    (net (code "53") (name "/SIG52") (class "Default")
      (node (ref "X1") (pin "B21") (pinfunction "B21_B21") (pintype "passive"))
      (node (ref "X2") (pin "B21") (pinfunction "B21_B21") (pintype "passive"))
      (node (ref "X3") (pin "B21") (pinfunction "B21_B21") (pintype "passive"))
      (node (ref "X4") (pin "B21") (pinfunction "B21_B21") (pintype "passive"))
      (node (ref "X5") (pin "B21") (pinfunction "B21_B21") (pintype "passive"))
      (node (ref "X6") (pin "B21") (pinfunction "B21_B21") (pintype "passive"))
      (node (ref "X7") (pin "B21") (pinfunction "B21_B21") (pintype "passive"))
    )
    (net (code "54") (name "/SIG53") (class "Default")
      (node (ref "X1") (pin "C21") (pinfunction "C21_C21") (pintype "passive"))
      (node (ref "X2") (pin "C21") (pinfunction "C21_C21") (pintype "passive"))
      (node (ref "X3") (pin "C21") (pinfunction "C21_C21") (pintype "passive"))
      (node (ref "X4") (pin "C21") (pinfunction "C21_C21") (pintype "passive"))
      (node (ref "X5") (pin "C21") (pinfunction "C21_C21") (pintype "passive"))
      (node (ref "X6") (pin "C21") (pinfunction "C21_C21") (pintype "passive"))
      (node (ref "X7") (pin "C21") (pinfunction "C21_C21") (pintype "passive"))
    )
    (net (code "55") (name "/SIG54") (class "Default")
      (node (ref "X1") (pin "A22") (pinfunction "A22_A22") (pintype "passive"))
      (node (ref "X2") (pin "A22") (pinfunction "A22_A22") (pintype "passive"))
      (node (ref "X3") (pin "A22") (pinfunction "A22_A22") (pintype "passive"))
      (node (ref "X4") (pin "A22") (pinfunction "A22_A22") (pintype "passive"))
      (node (ref "X5") (pin "A22") (pinfunction "A22_A22") (pintype "passive"))
      (node (ref "X6") (pin "A22") (pinfunction "A22_A22") (pintype "passive"))
      (node (ref "X7") (pin "A22") (pinfunction "A22_A22") (pintype "passive"))
    )
    (net (code "56") (name "/SIG55") (class "Default")
      (node (ref "X1") (pin "B22") (pinfunction "B22_B22") (pintype "passive"))
      (node (ref "X2") (pin "B22") (pinfunction "B22_B22") (pintype "passive"))
      (node (ref "X3") (pin "B22") (pinfunction "B22_B22") (pintype "passive"))
      (node (ref "X4") (pin "B22") (pinfunction "B22_B22") (pintype "passive"))
      (node (ref "X5") (pin "B22") (pinfunction "B22_B22") (pintype "passive"))
      (node (ref "X6") (pin "B22") (pinfunction "B22_B22") (pintype "passive"))
      (node (ref "X7") (pin "B22") (pinfunction "B22_B22") (pintype "passive"))
    )
    (net (code "57") (name "/SIG56") (class "Default")
      (node (ref "X1") (pin "C22") (pinfunction "C22_C22") (pintype "passive"))
      (node (ref "X2") (pin "C22") (pinfunction "C22_C22") (pintype "passive"))
      (node (ref "X3") (pin "C22") (pinfunction "C22_C22") (pintype "passive"))
      (node (ref "X4") (pin "C22") (pinfunction "C22_C22") (pintype "passive"))
      (node (ref "X5") (pin "C22") (pinfunction "C22_C22") (pintype "passive"))
      (node (ref "X6") (pin "C22") (pinfunction "C22_C22") (pintype "passive"))
      (node (ref "X7") (pin "C22") (pinfunction "C22_C22") (pintype "passive"))
    )
    (net (code "58") (name "/SIG57") (class "Default")
      (node (ref "X1") (pin "A23") (pinfunction "A23_A23") (pintype "passive"))
      (node (ref "X2") (pin "A23") (pinfunction "A23_A23") (pintype "passive"))
      (node (ref "X3") (pin "A23") (pinfunction "A23_A23") (pintype "passive"))
      (node (ref "X4") (pin "A23") (pinfunction "A23_A23") (pintype "passive"))
      (node (ref "X5") (pin "A23") (pinfunction "A23_A23") (pintype "passive"))
      (node (ref "X6") (pin "A23") (pinfunction "A23_A23") (pintype "passive"))
      (node (ref "X7") (pin "A23") (pinfunction "A23_A23") (pintype "passive"))
    )
    (net (code "59") (name "/SIG58") (class "Default")
      (node (ref "X1") (pin "B23") (pinfunction "B23_B23") (pintype "passive"))
      (node (ref "X2") (pin "B23") (pinfunction "B23_B23") (pintype "passive"))
      (node (ref "X3") (pin "B23") (pinfunction "B23_B23") (pintype "passive"))
      (node (ref "X4") (pin "B23") (pinfunction "B23_B23") (pintype "passive"))
      (node (ref "X5") (pin "B23") (pinfunction "B23_B23") (pintype "passive"))
      (node (ref "X6") (pin "B23") (pinfunction "B23_B23") (pintype "passive"))
      (node (ref "X7") (pin "B23") (pinfunction "B23_B23") (pintype "passive"))
    )
    (net (code "60") (name "/SIG59") (class "Default")
      (node (ref "X1") (pin "C23") (pinfunction "C23_C23") (pintype "passive"))
      (node (ref "X2") (pin "C23") (pinfunction "C23_C23") (pintype "passive"))
      (node (ref "X3") (pin "C23") (pinfunction "C23_C23") (pintype "passive"))
      (node (ref "X4") (pin "C23") (pinfunction "C23_C23") (pintype "passive"))
      (node (ref "X5") (pin "C23") (pinfunction "C23_C23") (pintype "passive"))
      (node (ref "X6") (pin "C23") (pinfunction "C23_C23") (pintype "passive"))
      (node (ref "X7") (pin "C23") (pinfunction "C23_C23") (pintype "passive"))
    )
    (net (code "61") (name "/SIG60") (class "Default")
      (node (ref "X1") (pin "A24") (pinfunction "A24_A24") (pintype "passive"))
      (node (ref "X2") (pin "A24") (pinfunction "A24_A24") (pintype "passive"))
      (node (ref "X3") (pin "A24") (pinfunction "A24_A24") (pintype "passive"))
      (node (ref "X4") (pin "A24") (pinfunction "A24_A24") (pintype "passive"))
      (node (ref "X5") (pin "A24") (pinfunction "A24_A24") (pintype "passive"))
      (node (ref "X6") (pin "A24") (pinfunction "A24_A24") (pintype "passive"))
      (node (ref "X7") (pin "A24") (pinfunction "A24_A24") (pintype "passive"))
    )
    (net (code "62") (name "/SIG61") (class "Default")
      (node (ref "X1") (pin "B24") (pinfunction "B24_B24") (pintype "passive"))
      (node (ref "X2") (pin "B24") (pinfunction "B24_B24") (pintype "passive"))
      (node (ref "X3") (pin "B24") (pinfunction "B24_B24") (pintype "passive"))
      (node (ref "X4") (pin "B24") (pinfunction "B24_B24") (pintype "passive"))
      (node (ref "X5") (pin "B24") (pinfunction "B24_B24") (pintype "passive"))
      (node (ref "X6") (pin "B24") (pinfunction "B24_B24") (pintype "passive"))
      (node (ref "X7") (pin "B24") (pinfunction "B24_B24") (pintype "passive"))
    )
    (net (code "63") (name "/SIG62") (class "Default")
      (node (ref "X1") (pin "C24") (pinfunction "C24_C24") (pintype "passive"))
      (node (ref "X2") (pin "C24") (pinfunction "C24_C24") (pintype "passive"))
      (node (ref "X3") (pin "C24") (pinfunction "C24_C24") (pintype "passive"))
      (node (ref "X4") (pin "C24") (pinfunction "C24_C24") (pintype "passive"))
      (node (ref "X5") (pin "C24") (pinfunction "C24_C24") (pintype "passive"))
      (node (ref "X6") (pin "C24") (pinfunction "C24_C24") (pintype "passive"))
      (node (ref "X7") (pin "C24") (pinfunction "C24_C24") (pintype "passive"))
    )
    (net (code "64") (name "/SIG63") (class "Default")
      (node (ref "X1") (pin "A25") (pinfunction "A25_A25") (pintype "passive"))
      (node (ref "X2") (pin "A25") (pinfunction "A25_A25") (pintype "passive"))
      (node (ref "X3") (pin "A25") (pinfunction "A25_A25") (pintype "passive"))
      (node (ref "X4") (pin "A25") (pinfunction "A25_A25") (pintype "passive"))
      (node (ref "X5") (pin "A25") (pinfunction "A25_A25") (pintype "passive"))
      (node (ref "X6") (pin "A25") (pinfunction "A25_A25") (pintype "passive"))
      (node (ref "X7") (pin "A25") (pinfunction "A25_A25") (pintype "passive"))
    )
    (net (code "65") (name "/SIG64") (class "Default")
      (node (ref "X1") (pin "B25") (pinfunction "B25_B25") (pintype "passive"))
      (node (ref "X2") (pin "B25") (pinfunction "B25_B25") (pintype "passive"))
      (node (ref "X3") (pin "B25") (pinfunction "B25_B25") (pintype "passive"))
      (node (ref "X4") (pin "B25") (pinfunction "B25_B25") (pintype "passive"))
      (node (ref "X5") (pin "B25") (pinfunction "B25_B25") (pintype "passive"))
      (node (ref "X6") (pin "B25") (pinfunction "B25_B25") (pintype "passive"))
      (node (ref "X7") (pin "B25") (pinfunction "B25_B25") (pintype "passive"))
    )
    (net (code "66") (name "/SIG65") (class "Default")
      (node (ref "X1") (pin "C25") (pinfunction "C25_C25") (pintype "passive"))
      (node (ref "X2") (pin "C25") (pinfunction "C25_C25") (pintype "passive"))
      (node (ref "X3") (pin "C25") (pinfunction "C25_C25") (pintype "passive"))
      (node (ref "X4") (pin "C25") (pinfunction "C25_C25") (pintype "passive"))
      (node (ref "X5") (pin "C25") (pinfunction "C25_C25") (pintype "passive"))
      (node (ref "X6") (pin "C25") (pinfunction "C25_C25") (pintype "passive"))
      (node (ref "X7") (pin "C25") (pinfunction "C25_C25") (pintype "passive"))
    )
    (net (code "67") (name "/SIG66") (class "Default")
      (node (ref "X1") (pin "A26") (pinfunction "A26_A26") (pintype "passive"))
      (node (ref "X2") (pin "A26") (pinfunction "A26_A26") (pintype "passive"))
      (node (ref "X3") (pin "A26") (pinfunction "A26_A26") (pintype "passive"))
      (node (ref "X4") (pin "A26") (pinfunction "A26_A26") (pintype "passive"))
      (node (ref "X5") (pin "A26") (pinfunction "A26_A26") (pintype "passive"))
      (node (ref "X6") (pin "A26") (pinfunction "A26_A26") (pintype "passive"))
      (node (ref "X7") (pin "A26") (pinfunction "A26_A26") (pintype "passive"))
    )
    (net (code "68") (name "/SIG67") (class "Default")
      (node (ref "X1") (pin "B26") (pinfunction "B26_B26") (pintype "passive"))
      (node (ref "X2") (pin "B26") (pinfunction "B26_B26") (pintype "passive"))
      (node (ref "X3") (pin "B26") (pinfunction "B26_B26") (pintype "passive"))
      (node (ref "X4") (pin "B26") (pinfunction "B26_B26") (pintype "passive"))
      (node (ref "X5") (pin "B26") (pinfunction "B26_B26") (pintype "passive"))
      (node (ref "X6") (pin "B26") (pinfunction "B26_B26") (pintype "passive"))
      (node (ref "X7") (pin "B26") (pinfunction "B26_B26") (pintype "passive"))
    )
    (net (code "69") (name "/SIG68") (class "Default")
      (node (ref "X1") (pin "C26") (pinfunction "C26_C26") (pintype "passive"))
      (node (ref "X2") (pin "C26") (pinfunction "C26_C26") (pintype "passive"))
      (node (ref "X3") (pin "C26") (pinfunction "C26_C26") (pintype "passive"))
      (node (ref "X4") (pin "C26") (pinfunction "C26_C26") (pintype "passive"))
      (node (ref "X5") (pin "C26") (pinfunction "C26_C26") (pintype "passive"))
      (node (ref "X6") (pin "C26") (pinfunction "C26_C26") (pintype "passive"))
      (node (ref "X7") (pin "C26") (pinfunction "C26_C26") (pintype "passive"))
    )
    (net (code "70") (name "/SIG69") (class "Default")
      (node (ref "X1") (pin "A27") (pinfunction "A27_A27") (pintype "passive"))
      (node (ref "X2") (pin "A27") (pinfunction "A27_A27") (pintype "passive"))
      (node (ref "X3") (pin "A27") (pinfunction "A27_A27") (pintype "passive"))
      (node (ref "X4") (pin "A27") (pinfunction "A27_A27") (pintype "passive"))
      (node (ref "X5") (pin "A27") (pinfunction "A27_A27") (pintype "passive"))
      (node (ref "X6") (pin "A27") (pinfunction "A27_A27") (pintype "passive"))
      (node (ref "X7") (pin "A27") (pinfunction "A27_A27") (pintype "passive"))
    )
    (net (code "71") (name "/SIG70") (class "Default")
      (node (ref "X1") (pin "B27") (pinfunction "B27_B27") (pintype "passive"))
      (node (ref "X2") (pin "B27") (pinfunction "B27_B27") (pintype "passive"))
      (node (ref "X3") (pin "B27") (pinfunction "B27_B27") (pintype "passive"))
      (node (ref "X4") (pin "B27") (pinfunction "B27_B27") (pintype "passive"))
      (node (ref "X5") (pin "B27") (pinfunction "B27_B27") (pintype "passive"))
      (node (ref "X6") (pin "B27") (pinfunction "B27_B27") (pintype "passive"))
      (node (ref "X7") (pin "B27") (pinfunction "B27_B27") (pintype "passive"))
    )
    (net (code "72") (name "/SIG71") (class "Default")
      (node (ref "X1") (pin "C27") (pinfunction "C27_C27") (pintype "passive"))
      (node (ref "X2") (pin "C27") (pinfunction "C27_C27") (pintype "passive"))
      (node (ref "X3") (pin "C27") (pinfunction "C27_C27") (pintype "passive"))
      (node (ref "X4") (pin "C27") (pinfunction "C27_C27") (pintype "passive"))
      (node (ref "X5") (pin "C27") (pinfunction "C27_C27") (pintype "passive"))
      (node (ref "X6") (pin "C27") (pinfunction "C27_C27") (pintype "passive"))
      (node (ref "X7") (pin "C27") (pinfunction "C27_C27") (pintype "passive"))
    )
    (net (code "73") (name "/SIG72") (class "Default")
      (node (ref "X1") (pin "A28") (pinfunction "A28_A28") (pintype "passive"))
      (node (ref "X2") (pin "A28") (pinfunction "A28_A28") (pintype "passive"))
      (node (ref "X3") (pin "A28") (pinfunction "A28_A28") (pintype "passive"))
      (node (ref "X4") (pin "A28") (pinfunction "A28_A28") (pintype "passive"))
      (node (ref "X5") (pin "A28") (pinfunction "A28_A28") (pintype "passive"))
      (node (ref "X6") (pin "A28") (pinfunction "A28_A28") (pintype "passive"))
      (node (ref "X7") (pin "A28") (pinfunction "A28_A28") (pintype "passive"))
    )
    (net (code "74") (name "/SIG73") (class "Default")
      (node (ref "X1") (pin "B28") (pinfunction "B28_B28") (pintype "passive"))
      (node (ref "X2") (pin "B28") (pinfunction "B28_B28") (pintype "passive"))
      (node (ref "X3") (pin "B28") (pinfunction "B28_B28") (pintype "passive"))
      (node (ref "X4") (pin "B28") (pinfunction "B28_B28") (pintype "passive"))
      (node (ref "X5") (pin "B28") (pinfunction "B28_B28") (pintype "passive"))
      (node (ref "X6") (pin "B28") (pinfunction "B28_B28") (pintype "passive"))
      (node (ref "X7") (pin "B28") (pinfunction "B28_B28") (pintype "passive"))
    )
    (net (code "75") (name "/SIG74") (class "Default")
      (node (ref "X1") (pin "C28") (pinfunction "C28_C28") (pintype "passive"))
      (node (ref "X2") (pin "C28") (pinfunction "C28_C28") (pintype "passive"))
      (node (ref "X3") (pin "C28") (pinfunction "C28_C28") (pintype "passive"))
      (node (ref "X4") (pin "C28") (pinfunction "C28_C28") (pintype "passive"))
      (node (ref "X5") (pin "C28") (pinfunction "C28_C28") (pintype "passive"))
      (node (ref "X6") (pin "C28") (pinfunction "C28_C28") (pintype "passive"))
      (node (ref "X7") (pin "C28") (pinfunction "C28_C28") (pintype "passive"))
    )
    (net (code "76") (name "/SIG75") (class "Default")
      (node (ref "X1") (pin "A29") (pinfunction "A29_A29") (pintype "passive"))
      (node (ref "X2") (pin "A29") (pinfunction "A29_A29") (pintype "passive"))
      (node (ref "X3") (pin "A29") (pinfunction "A29_A29") (pintype "passive"))
      (node (ref "X4") (pin "A29") (pinfunction "A29_A29") (pintype "passive"))
      (node (ref "X5") (pin "A29") (pinfunction "A29_A29") (pintype "passive"))
      (node (ref "X6") (pin "A29") (pinfunction "A29_A29") (pintype "passive"))
      (node (ref "X7") (pin "A29") (pinfunction "A29_A29") (pintype "passive"))
    )
    (net (code "77") (name "/SIG76") (class "Default")
      (node (ref "X1") (pin "B29") (pinfunction "B29_B29") (pintype "passive"))
      (node (ref "X2") (pin "B29") (pinfunction "B29_B29") (pintype "passive"))
      (node (ref "X3") (pin "B29") (pinfunction "B29_B29") (pintype "passive"))
      (node (ref "X4") (pin "B29") (pinfunction "B29_B29") (pintype "passive"))
      (node (ref "X5") (pin "B29") (pinfunction "B29_B29") (pintype "passive"))
      (node (ref "X6") (pin "B29") (pinfunction "B29_B29") (pintype "passive"))
      (node (ref "X7") (pin "B29") (pinfunction "B29_B29") (pintype "passive"))
    )
    (net (code "78") (name "/SIG77") (class "Default")
      (node (ref "X1") (pin "C29") (pinfunction "C29_C29") (pintype "passive"))
      (node (ref "X2") (pin "C29") (pinfunction "C29_C29") (pintype "passive"))
      (node (ref "X3") (pin "C29") (pinfunction "C29_C29") (pintype "passive"))
      (node (ref "X4") (pin "C29") (pinfunction "C29_C29") (pintype "passive"))
      (node (ref "X5") (pin "C29") (pinfunction "C29_C29") (pintype "passive"))
      (node (ref "X6") (pin "C29") (pinfunction "C29_C29") (pintype "passive"))
      (node (ref "X7") (pin "C29") (pinfunction "C29_C29") (pintype "passive"))
    )
    (net (code "79") (name "/SIG78") (class "Default")
      (node (ref "X1") (pin "A30") (pinfunction "A30_A30") (pintype "passive"))
      (node (ref "X2") (pin "A30") (pinfunction "A30_A30") (pintype "passive"))
      (node (ref "X3") (pin "A30") (pinfunction "A30_A30") (pintype "passive"))
      (node (ref "X4") (pin "A30") (pinfunction "A30_A30") (pintype "passive"))
      (node (ref "X5") (pin "A30") (pinfunction "A30_A30") (pintype "passive"))
      (node (ref "X6") (pin "A30") (pinfunction "A30_A30") (pintype "passive"))
      (node (ref "X7") (pin "A30") (pinfunction "A30_A30") (pintype "passive"))
    )
    (net (code "80") (name "/SIG79") (class "Default")
      (node (ref "X1") (pin "B30") (pinfunction "B30_B30") (pintype "passive"))
      (node (ref "X2") (pin "B30") (pinfunction "B30_B30") (pintype "passive"))
      (node (ref "X3") (pin "B30") (pinfunction "B30_B30") (pintype "passive"))
      (node (ref "X4") (pin "B30") (pinfunction "B30_B30") (pintype "passive"))
      (node (ref "X5") (pin "B30") (pinfunction "B30_B30") (pintype "passive"))
      (node (ref "X6") (pin "B30") (pinfunction "B30_B30") (pintype "passive"))
      (node (ref "X7") (pin "B30") (pinfunction "B30_B30") (pintype "passive"))
    )
    (net (code "81") (name "/SIG80") (class "Default")
      (node (ref "X1") (pin "C30") (pinfunction "C30_C30") (pintype "passive"))
      (node (ref "X2") (pin "C30") (pinfunction "C30_C30") (pintype "passive"))
      (node (ref "X3") (pin "C30") (pinfunction "C30_C30") (pintype "passive"))
      (node (ref "X4") (pin "C30") (pinfunction "C30_C30") (pintype "passive"))
      (node (ref "X5") (pin "C30") (pinfunction "C30_C30") (pintype "passive"))
      (node (ref "X6") (pin "C30") (pinfunction "C30_C30") (pintype "passive"))
      (node (ref "X7") (pin "C30") (pinfunction "C30_C30") (pintype "passive"))
    )
    (net (code "82") (name "5V") (class "Default")
      (node (ref "5V") (pin "1") (pinfunction "P_1") (pintype "passive"))
      (node (ref "R1") (pin "2") (pinfunction "2_2") (pintype "passive"))
      (node (ref "X1") (pin "A2") (pinfunction "A2_A2") (pintype "passive"))
      (node (ref "X1") (pin "A31") (pinfunction "A31_A31") (pintype "passive"))
      (node (ref "X1") (pin "B2") (pinfunction "B2_B2") (pintype "passive"))
      (node (ref "X1") (pin "B31") (pinfunction "B31_B31") (pintype "passive"))
      (node (ref "X1") (pin "C2") (pinfunction "C2_C2") (pintype "passive"))
      (node (ref "X1") (pin "C31") (pinfunction "C31_C31") (pintype "passive"))
      (node (ref "X2") (pin "A2") (pinfunction "A2_A2") (pintype "passive"))
      (node (ref "X2") (pin "A31") (pinfunction "A31_A31") (pintype "passive"))
      (node (ref "X2") (pin "B2") (pinfunction "B2_B2") (pintype "passive"))
      (node (ref "X2") (pin "B31") (pinfunction "B31_B31") (pintype "passive"))
      (node (ref "X2") (pin "C2") (pinfunction "C2_C2") (pintype "passive"))
      (node (ref "X2") (pin "C31") (pinfunction "C31_C31") (pintype "passive"))
      (node (ref "X3") (pin "A2") (pinfunction "A2_A2") (pintype "passive"))
      (node (ref "X3") (pin "A31") (pinfunction "A31_A31") (pintype "passive"))
      (node (ref "X3") (pin "B2") (pinfunction "B2_B2") (pintype "passive"))
      (node (ref "X3") (pin "B31") (pinfunction "B31_B31") (pintype "passive"))
      (node (ref "X3") (pin "C2") (pinfunction "C2_C2") (pintype "passive"))
      (node (ref "X3") (pin "C31") (pinfunction "C31_C31") (pintype "passive"))
      (node (ref "X4") (pin "A2") (pinfunction "A2_A2") (pintype "passive"))
      (node (ref "X4") (pin "A31") (pinfunction "A31_A31") (pintype "passive"))
      (node (ref "X4") (pin "B2") (pinfunction "B2_B2") (pintype "passive"))
      (node (ref "X4") (pin "B31") (pinfunction "B31_B31") (pintype "passive"))
      (node (ref "X4") (pin "C2") (pinfunction "C2_C2") (pintype "passive"))
      (node (ref "X4") (pin "C31") (pinfunction "C31_C31") (pintype "passive"))
      (node (ref "X5") (pin "A2") (pinfunction "A2_A2") (pintype "passive"))
      (node (ref "X5") (pin "A31") (pinfunction "A31_A31") (pintype "passive"))
      (node (ref "X5") (pin "B2") (pinfunction "B2_B2") (pintype "passive"))
      (node (ref "X5") (pin "B31") (pinfunction "B31_B31") (pintype "passive"))
      (node (ref "X5") (pin "C2") (pinfunction "C2_C2") (pintype "passive"))
      (node (ref "X5") (pin "C31") (pinfunction "C31_C31") (pintype "passive"))
      (node (ref "X6") (pin "A2") (pinfunction "A2_A2") (pintype "passive"))
      (node (ref "X6") (pin "A31") (pinfunction "A31_A31") (pintype "passive"))
      (node (ref "X6") (pin "B2") (pinfunction "B2_B2") (pintype "passive"))
      (node (ref "X6") (pin "B31") (pinfunction "B31_B31") (pintype "passive"))
      (node (ref "X6") (pin "C2") (pinfunction "C2_C2") (pintype "passive"))
      (node (ref "X6") (pin "C31") (pinfunction "C31_C31") (pintype "passive"))
      (node (ref "X7") (pin "A2") (pinfunction "A2_A2") (pintype "passive"))
      (node (ref "X7") (pin "A31") (pinfunction "A31_A31") (pintype "passive"))
      (node (ref "X7") (pin "B2") (pinfunction "B2_B2") (pintype "passive"))
      (node (ref "X7") (pin "B31") (pinfunction "B31_B31") (pintype "passive"))
      (node (ref "X7") (pin "C2") (pinfunction "C2_C2") (pintype "passive"))
      (node (ref "X7") (pin "C31") (pinfunction "C31_C31") (pintype "passive"))
    )
    (net (code "83") (name "12V") (class "Default")
      (node (ref "12V") (pin "1") (pinfunction "P_1") (pintype "passive"))
      (node (ref "X1") (pin "A3") (pinfunction "A3_A3") (pintype "passive"))
      (node (ref "X1") (pin "B3") (pinfunction "B3_B3") (pintype "passive"))
      (node (ref "X1") (pin "C3") (pinfunction "C3_C3") (pintype "passive"))
      (node (ref "X2") (pin "A3") (pinfunction "A3_A3") (pintype "passive"))
      (node (ref "X2") (pin "B3") (pinfunction "B3_B3") (pintype "passive"))
      (node (ref "X2") (pin "C3") (pinfunction "C3_C3") (pintype "passive"))
      (node (ref "X3") (pin "A3") (pinfunction "A3_A3") (pintype "passive"))
      (node (ref "X3") (pin "B3") (pinfunction "B3_B3") (pintype "passive"))
      (node (ref "X3") (pin "C3") (pinfunction "C3_C3") (pintype "passive"))
      (node (ref "X4") (pin "A3") (pinfunction "A3_A3") (pintype "passive"))
      (node (ref "X4") (pin "B3") (pinfunction "B3_B3") (pintype "passive"))
      (node (ref "X4") (pin "C3") (pinfunction "C3_C3") (pintype "passive"))
      (node (ref "X5") (pin "A3") (pinfunction "A3_A3") (pintype "passive"))
      (node (ref "X5") (pin "B3") (pinfunction "B3_B3") (pintype "passive"))
      (node (ref "X5") (pin "C3") (pinfunction "C3_C3") (pintype "passive"))
      (node (ref "X6") (pin "A3") (pinfunction "A3_A3") (pintype "passive"))
      (node (ref "X6") (pin "B3") (pinfunction "B3_B3") (pintype "passive"))
      (node (ref "X6") (pin "C3") (pinfunction "C3_C3") (pintype "passive"))
      (node (ref "X7") (pin "A3") (pinfunction "A3_A3") (pintype "passive"))
      (node (ref "X7") (pin "B3") (pinfunction "B3_B3") (pintype "passive"))
      (node (ref "X7") (pin "C3") (pinfunction "C3_C3") (pintype "passive"))
    )
    (net (code "84") (name "GND") (class "Default")
      (node (ref "GND") (pin "1") (pinfunction "P_1") (pintype "passive"))
      (node (ref "PWR") (pin "K") (pinfunction "C_K") (pintype "passive"))
      (node (ref "X1") (pin "A1") (pinfunction "A1_A1") (pintype "passive"))
      (node (ref "X1") (pin "A32") (pinfunction "A32_A32") (pintype "passive"))
      (node (ref "X1") (pin "B1") (pinfunction "B1_B1") (pintype "passive"))
      (node (ref "X1") (pin "B32") (pinfunction "B32_B32") (pintype "passive"))
      (node (ref "X1") (pin "C1") (pinfunction "C1_C1") (pintype "passive"))
      (node (ref "X1") (pin "C32") (pinfunction "C32_C32") (pintype "passive"))
      (node (ref "X2") (pin "A1") (pinfunction "A1_A1") (pintype "passive"))
      (node (ref "X2") (pin "A32") (pinfunction "A32_A32") (pintype "passive"))
      (node (ref "X2") (pin "B1") (pinfunction "B1_B1") (pintype "passive"))
      (node (ref "X2") (pin "B32") (pinfunction "B32_B32") (pintype "passive"))
      (node (ref "X2") (pin "C1") (pinfunction "C1_C1") (pintype "passive"))
      (node (ref "X2") (pin "C32") (pinfunction "C32_C32") (pintype "passive"))
      (node (ref "X3") (pin "A1") (pinfunction "A1_A1") (pintype "passive"))
      (node (ref "X3") (pin "A32") (pinfunction "A32_A32") (pintype "passive"))
      (node (ref "X3") (pin "B1") (pinfunction "B1_B1") (pintype "passive"))
      (node (ref "X3") (pin "B32") (pinfunction "B32_B32") (pintype "passive"))
      (node (ref "X3") (pin "C1") (pinfunction "C1_C1") (pintype "passive"))
      (node (ref "X3") (pin "C32") (pinfunction "C32_C32") (pintype "passive"))
      (node (ref "X4") (pin "A1") (pinfunction "A1_A1") (pintype "passive"))
      (node (ref "X4") (pin "A32") (pinfunction "A32_A32") (pintype "passive"))
      (node (ref "X4") (pin "B1") (pinfunction "B1_B1") (pintype "passive"))
      (node (ref "X4") (pin "B32") (pinfunction "B32_B32") (pintype "passive"))
      (node (ref "X4") (pin "C1") (pinfunction "C1_C1") (pintype "passive"))
      (node (ref "X4") (pin "C32") (pinfunction "C32_C32") (pintype "passive"))
      (node (ref "X5") (pin "A1") (pinfunction "A1_A1") (pintype "passive"))
      (node (ref "X5") (pin "A32") (pinfunction "A32_A32") (pintype "passive"))
      (node (ref "X5") (pin "B1") (pinfunction "B1_B1") (pintype "passive"))
      (node (ref "X5") (pin "B32") (pinfunction "B32_B32") (pintype "passive"))
      (node (ref "X5") (pin "C1") (pinfunction "C1_C1") (pintype "passive"))
      (node (ref "X5") (pin "C32") (pinfunction "C32_C32") (pintype "passive"))
      (node (ref "X6") (pin "A1") (pinfunction "A1_A1") (pintype "passive"))
      (node (ref "X6") (pin "A32") (pinfunction "A32_A32") (pintype "passive"))
      (node (ref "X6") (pin "B1") (pinfunction "B1_B1") (pintype "passive"))
      (node (ref "X6") (pin "B32") (pinfunction "B32_B32") (pintype "passive"))
      (node (ref "X6") (pin "C1") (pinfunction "C1_C1") (pintype "passive"))
      (node (ref "X6") (pin "C32") (pinfunction "C32_C32") (pintype "passive"))
      (node (ref "X7") (pin "A1") (pinfunction "A1_A1") (pintype "passive"))
      (node (ref "X7") (pin "A32") (pinfunction "A32_A32") (pintype "passive"))
      (node (ref "X7") (pin "B1") (pinfunction "B1_B1") (pintype "passive"))
      (node (ref "X7") (pin "B32") (pinfunction "B32_B32") (pintype "passive"))
      (node (ref "X7") (pin "C1") (pinfunction "C1_C1") (pintype "passive"))
      (node (ref "X7") (pin "C32") (pinfunction "C32_C32") (pintype "passive"))
    )
    (net (code "85") (name "Net-(PWR-PadA)") (class "Default")
      (node (ref "PWR") (pin "A") (pinfunction "A_A") (pintype "passive"))
      (node (ref "R1") (pin "1") (pinfunction "1_1") (pintype "passive"))
    )
  )
)
